# MCU_STM32H723ZGT6.net
KiCad netlist of a schematic drawn in Altium Designer
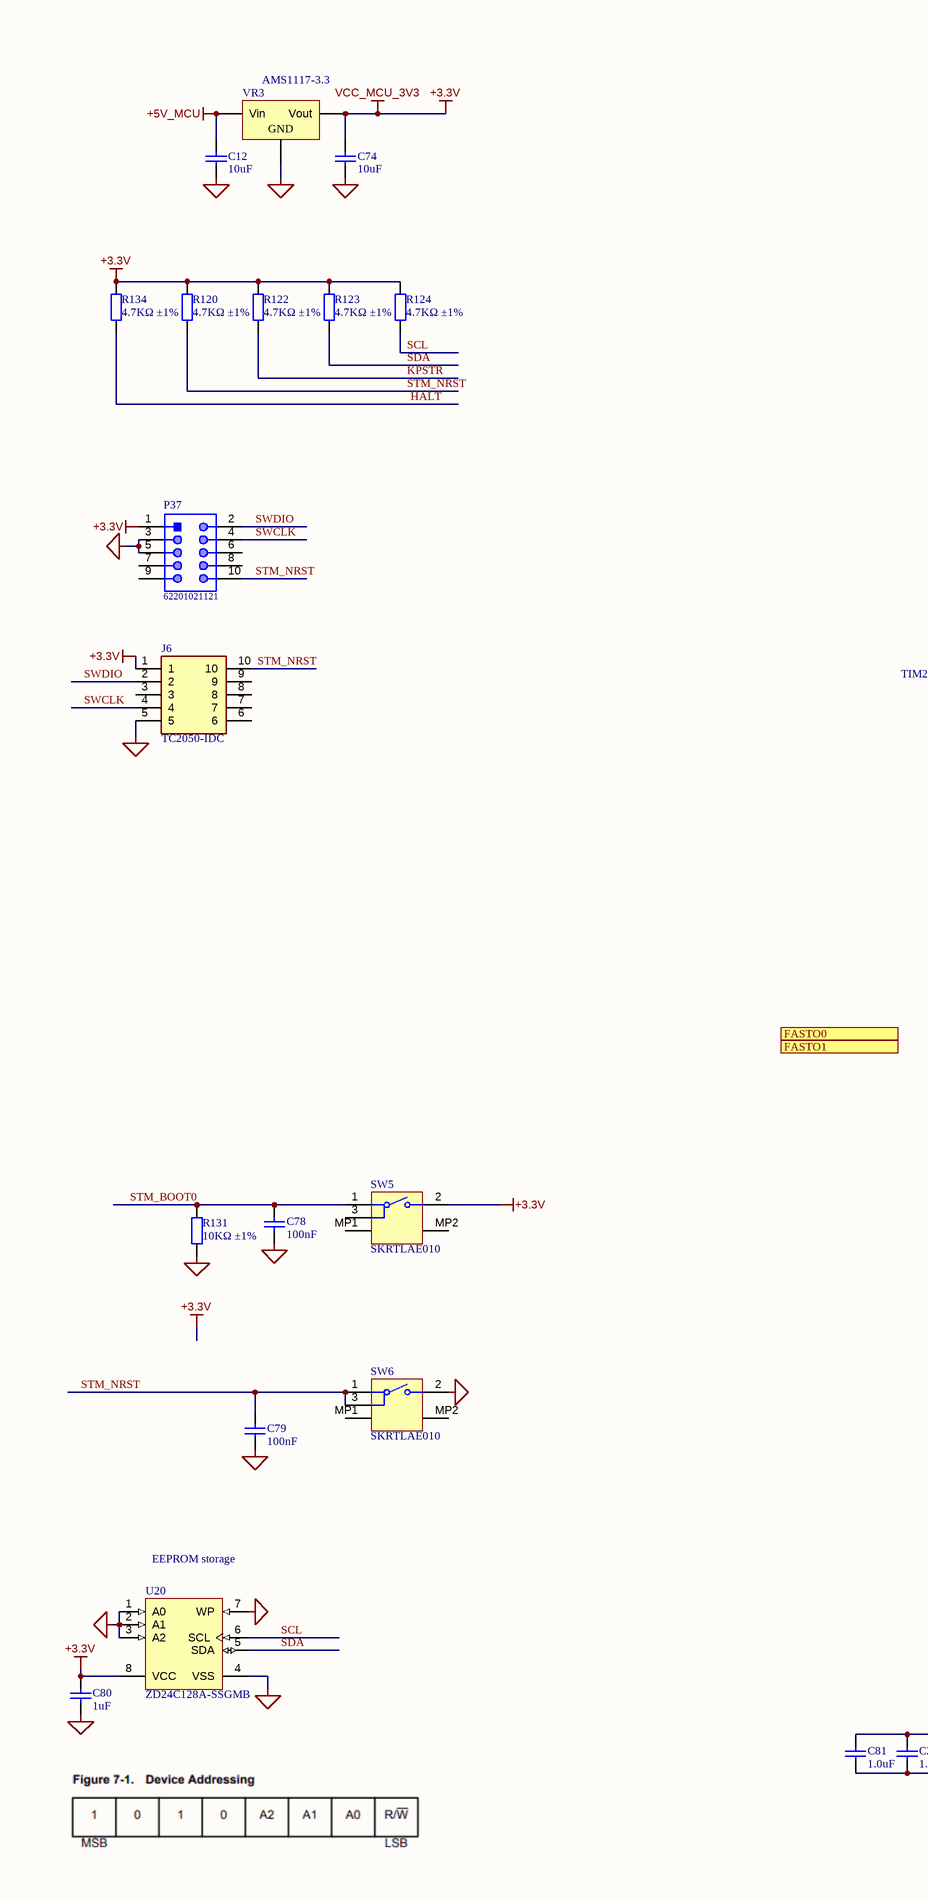
[diagram p0: MCU_STM32H723ZGT6.SchDoc, left]
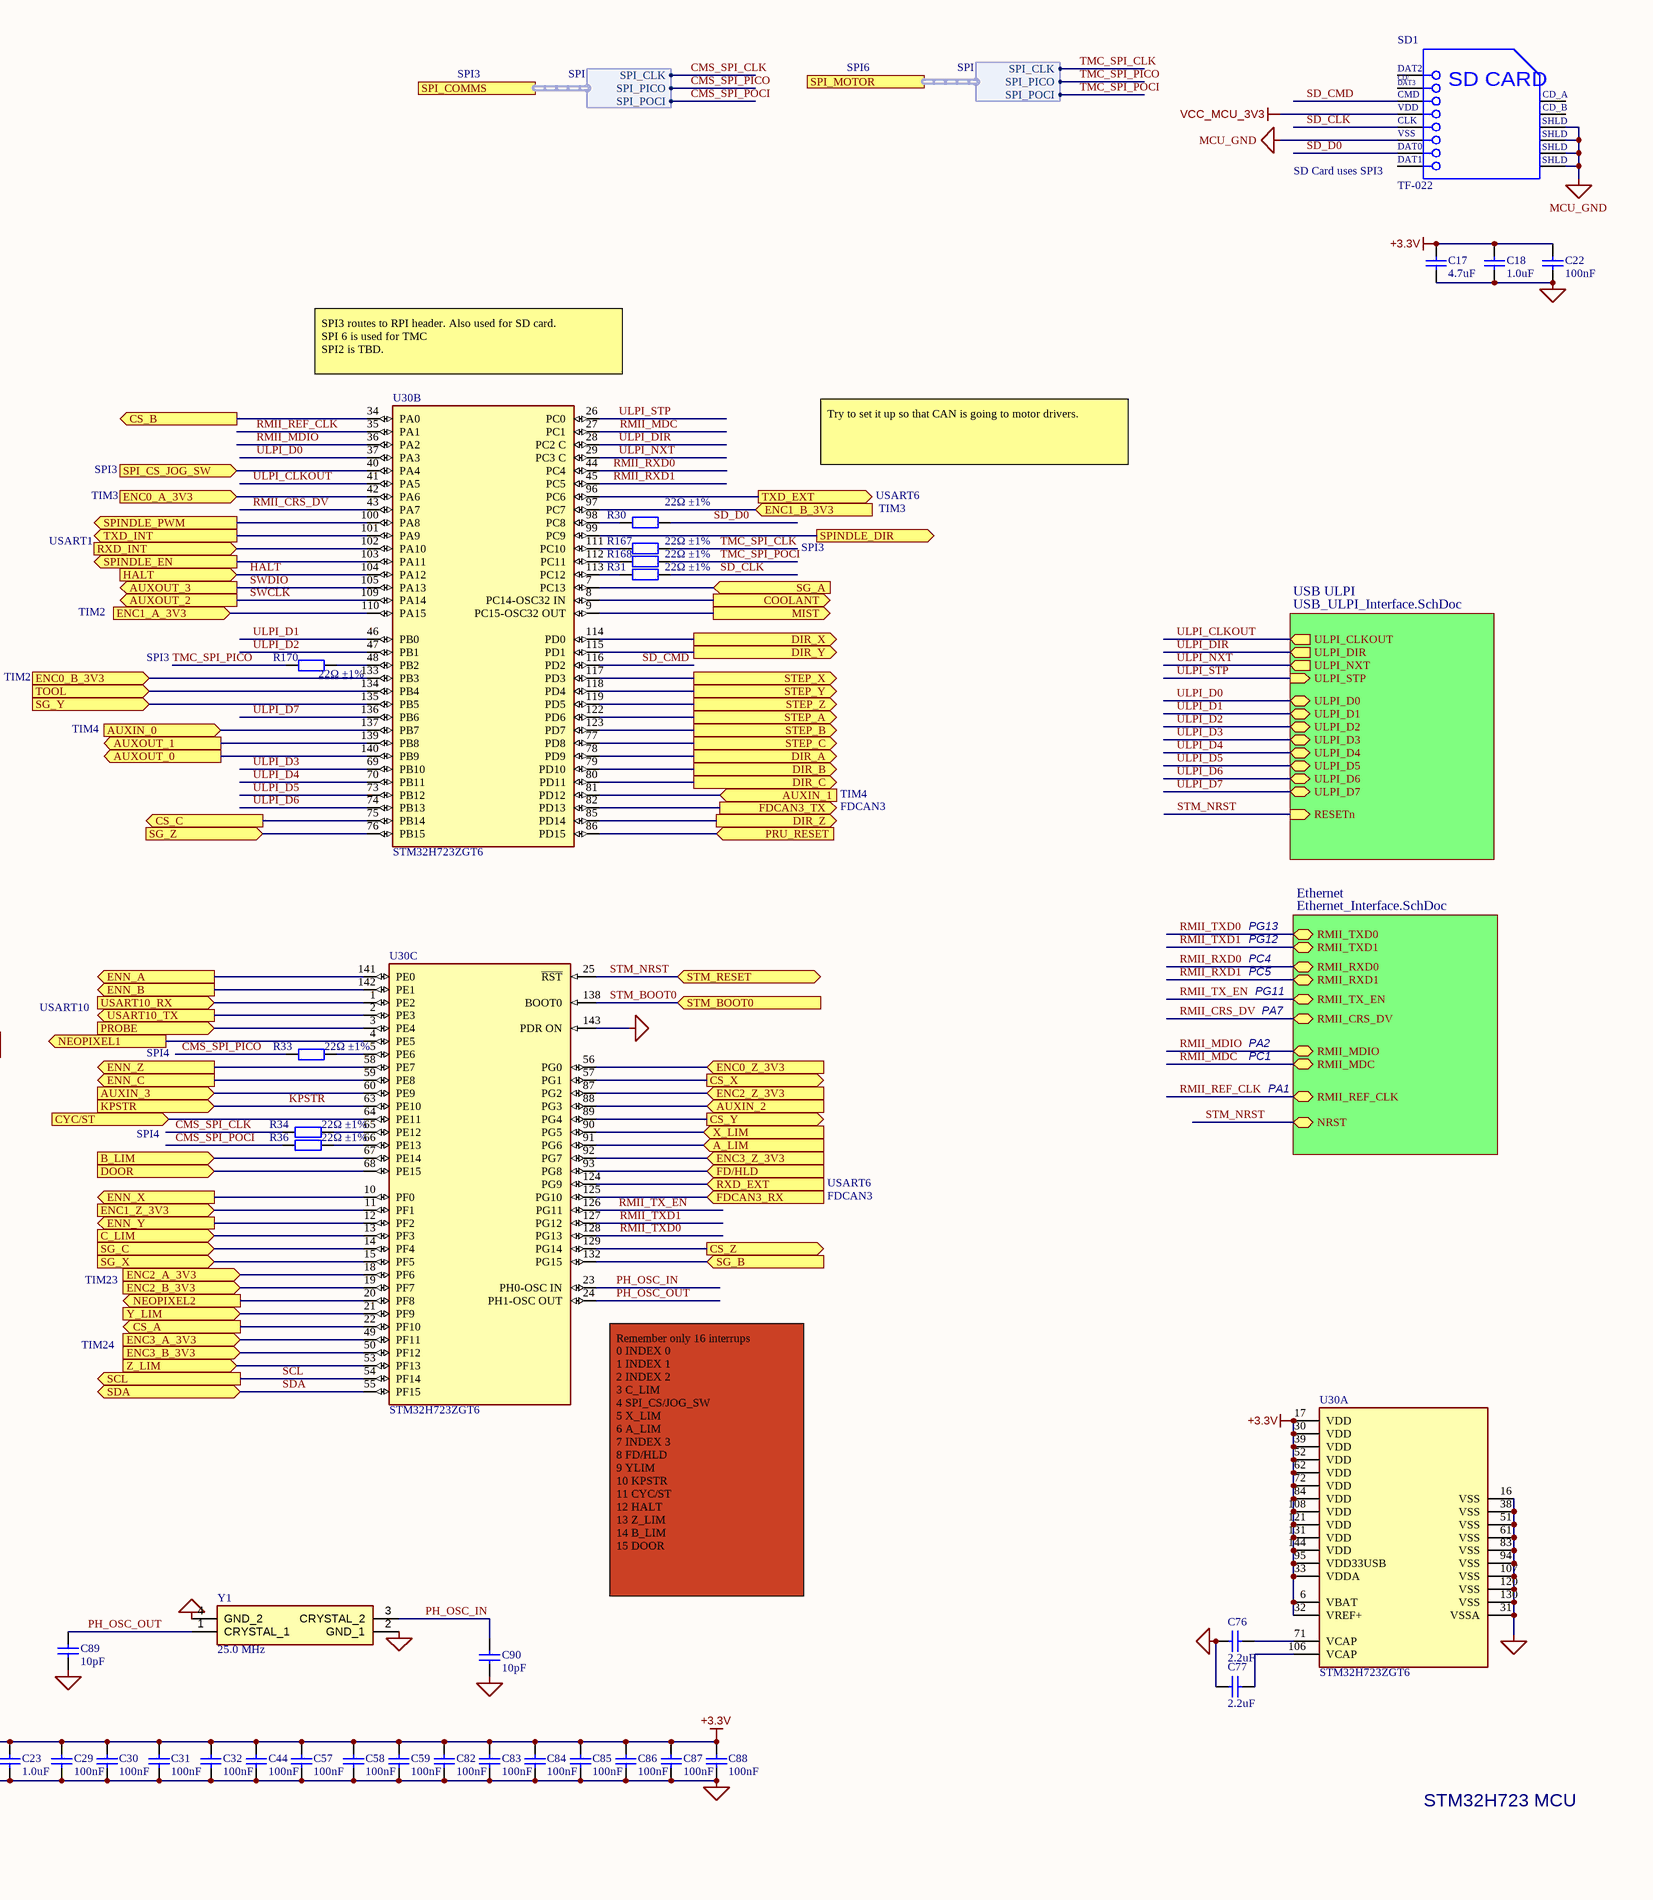
[diagram p1: MCU_STM32H723ZGT6.SchDoc, right]

(export (version "E")
  (design (tool "Eeschema 10.0.6"))
  (components
    (comp (ref "C12")
      (value "10uF")
      (footprint "1206_C")
      (description "Chip capacitors")
      (fields
        (field (name "MANUFACTURER") "Samsung Electro-Mechanics")
        (field (name "PARTNUMBER") "CL31A106KBHNNNE")
      )
      (libsource (lib "Cap") (part "1206 10uF (106) 10% 50V"))
    )
    (comp (ref "C17")
      (value "4.7uF")
      (footprint "0603_C")
      (description "16V 4.7uF X5R ±10% 0603 Multilayer Ceramic Capacitors MLCC - SMD/SMT ROHS")
      (fields (field (name "MANUFACTURER") "Samsung Electro-Mechanics") (field (name "TOLERANCE") "10%"))
      (libsource (lib "Sienci_Labs") (part "0603 4.7uF (475) 10% 16V"))
    )
    (comp (ref "C18")
      (value "1.0uF")
      (footprint "0402_C")
      (description "Chip capacitor")
      (fields (field (name "MANUFACTURER") "Samsung Electro-Mechanics") (field (name "TOLERANCE") "10%"))
      (libsource (lib "Cap") (part "0402 1.0uF (105) 10% 25V"))
    )
    (comp (ref "C22")
      (value "100nF")
      (footprint "0402_C")
      (description "16V 100nF X7R ±10% 0402 Multilayer Ceramic Capacitors MLCC - SMD/SMT ROHS")
      (fields (field (name "MANUFACTURER") "Samsung Electro-Mechanics") (field (name "TOLERANCE") "10%"))
      (libsource (lib "Sienci_Labs") (part "0402 100nF (104) 10% 16V"))
    )
    (comp (ref "C23")
      (value "1.0uF")
      (footprint "0402_C")
      (description "Chip capacitor")
      (fields
        (field (name "MANUFACTURER") "Samsung Electro-Mechanics")
        (field (name "PARTNUMBER") "CL05A105KA5NQNC")
      )
      (libsource (lib "Cap") (part "0402 1.0uF (105) 10% 25V"))
    )
    (comp (ref "C29")
      (value "100nF")
      (footprint "0402_C")
      (description "Chip capacitors")
      (fields
        (field (name "MANUFACTURER") "Samsung Electro-Mechanics")
        (field (name "PARTNUMBER") "CL05B104KO5NNNC")
      )
      (libsource (lib "Cap") (part "0402 100nF (104) 10% 16V"))
    )
    (comp (ref "C30")
      (value "100nF")
      (footprint "0402_C")
      (description "Chip capacitors")
      (fields
        (field (name "MANUFACTURER") "Samsung Electro-Mechanics")
        (field (name "PARTNUMBER") "CL05B104KO5NNNC")
      )
      (libsource (lib "Cap") (part "0402 100nF (104) 10% 16V"))
    )
    (comp (ref "C31")
      (value "100nF")
      (footprint "0402_C")
      (description "Chip capacitors")
      (fields
        (field (name "MANUFACTURER") "Samsung Electro-Mechanics")
        (field (name "PARTNUMBER") "CL05B104KO5NNNC")
      )
      (libsource (lib "Cap") (part "0402 100nF (104) 10% 16V"))
    )
    (comp (ref "C32")
      (value "100nF")
      (footprint "0402_C")
      (description "Chip capacitors")
      (fields
        (field (name "MANUFACTURER") "Samsung Electro-Mechanics")
        (field (name "PARTNUMBER") "CL05B104KO5NNNC")
      )
      (libsource (lib "Cap") (part "0402 100nF (104) 10% 16V"))
    )
    (comp (ref "C44")
      (value "100nF")
      (footprint "0402_C")
      (description "Chip capacitors")
      (fields
        (field (name "MANUFACTURER") "Samsung Electro-Mechanics")
        (field (name "PARTNUMBER") "CL05B104KO5NNNC")
      )
      (libsource (lib "Cap") (part "0402 100nF (104) 10% 16V"))
    )
    (comp (ref "C57")
      (value "100nF")
      (footprint "0402_C")
      (description "Chip capacitors")
      (fields
        (field (name "MANUFACTURER") "Samsung Electro-Mechanics")
        (field (name "PARTNUMBER") "CL05B104KO5NNNC")
      )
      (libsource (lib "Cap") (part "0402 100nF (104) 10% 16V"))
    )
    (comp (ref "C58")
      (value "100nF")
      (footprint "0402_C")
      (description "Chip capacitors")
      (fields
        (field (name "MANUFACTURER") "Samsung Electro-Mechanics")
        (field (name "PARTNUMBER") "CL05B104KO5NNNC")
      )
      (libsource (lib "Cap") (part "0402 100nF (104) 10% 16V"))
    )
    (comp (ref "C59")
      (value "100nF")
      (footprint "0402_C")
      (description "Chip capacitors")
      (fields
        (field (name "MANUFACTURER") "Samsung Electro-Mechanics")
        (field (name "PARTNUMBER") "CL05B104KO5NNNC")
      )
      (libsource (lib "Cap") (part "0402 100nF (104) 10% 16V"))
    )
    (comp (ref "C74")
      (value "10uF")
      (footprint "1206_C")
      (description "Chip capacitors")
      (fields
        (field (name "MANUFACTURER") "Samsung Electro-Mechanics")
        (field (name "PARTNUMBER") "CL31A106KBHNNNE")
      )
      (libsource (lib "Cap") (part "1206 10uF (106) 10% 50V"))
    )
    (comp (ref "C76")
      (value "2.2uF")
      (footprint "0603_C")
      (description "Chip capacitors")
      (fields
        (field (name "MANUFACTURER") "Samsung Electro-Mechanics")
        (field (name "PARTNUMBER") "CL10A225KO8NNNC")
      )
      (libsource (lib "Cap") (part "0603 2.2uF (225) 10% 16V"))
    )
    (comp (ref "C77")
      (value "2.2uF")
      (footprint "0603_C")
      (description "Chip capacitors")
      (fields
        (field (name "MANUFACTURER") "Samsung Electro-Mechanics")
        (field (name "PARTNUMBER") "CL10A225KO8NNNC")
      )
      (libsource (lib "Cap") (part "0603 2.2uF (225) 10% 16V"))
    )
    (comp (ref "C78")
      (value "100nF")
      (footprint "0603_C")
      (description "Chip capacitors")
      (fields (field (name "MANUFACTURER") "YAGEO") (field (name "PARTNUMBER") "CC0603KRX7R9BB104"))
      (libsource (lib "Cap") (part "0603 100nF (104) 10% 50V"))
    )
    (comp (ref "C79")
      (value "100nF")
      (footprint "0603_C")
      (description "Chip capacitors")
      (fields (field (name "MANUFACTURER") "YAGEO") (field (name "PARTNUMBER") "CC0603KRX7R9BB104"))
      (libsource (lib "Cap") (part "0603 100nF (104) 10% 50V"))
    )
    (comp (ref "C80")
      (value "1uF")
      (footprint "0603_C")
      (description "Chip capacitors")
      (fields
        (field (name "MANUFACTURER") "Samsung Electro-Mechanics")
        (field (name "PARTNUMBER") "CL10A105KB8NNNC")
      )
      (libsource (lib "Cap") (part "0603 1uF (105) 10% 50V"))
    )
    (comp (ref "C81")
      (value "1.0uF")
      (footprint "0402_C")
      (description "Chip capacitor")
      (fields
        (field (name "MANUFACTURER") "Samsung Electro-Mechanics")
        (field (name "PARTNUMBER") "CL05A105KA5NQNC")
      )
      (libsource (lib "Cap") (part "0402 1.0uF (105) 10% 25V"))
    )
    (comp (ref "C82")
      (value "100nF")
      (footprint "0402_C")
      (description "Chip capacitors")
      (fields
        (field (name "MANUFACTURER") "Samsung Electro-Mechanics")
        (field (name "PARTNUMBER") "CL05B104KO5NNNC")
      )
      (libsource (lib "Cap") (part "0402 100nF (104) 10% 16V"))
    )
    (comp (ref "C83")
      (value "100nF")
      (footprint "0402_C")
      (description "Chip capacitors")
      (fields
        (field (name "MANUFACTURER") "Samsung Electro-Mechanics")
        (field (name "PARTNUMBER") "CL05B104KO5NNNC")
      )
      (libsource (lib "Cap") (part "0402 100nF (104) 10% 16V"))
    )
    (comp (ref "C84")
      (value "100nF")
      (footprint "0402_C")
      (description "Chip capacitors")
      (fields
        (field (name "MANUFACTURER") "Samsung Electro-Mechanics")
        (field (name "PARTNUMBER") "CL05B104KO5NNNC")
      )
      (libsource (lib "Cap") (part "0402 100nF (104) 10% 16V"))
    )
    (comp (ref "C85")
      (value "100nF")
      (footprint "0402_C")
      (description "Chip capacitors")
      (fields
        (field (name "MANUFACTURER") "Samsung Electro-Mechanics")
        (field (name "PARTNUMBER") "CL05B104KO5NNNC")
      )
      (libsource (lib "Cap") (part "0402 100nF (104) 10% 16V"))
    )
    (comp (ref "C86")
      (value "100nF")
      (footprint "0402_C")
      (description "Chip capacitors")
      (fields
        (field (name "MANUFACTURER") "Samsung Electro-Mechanics")
        (field (name "PARTNUMBER") "CL05B104KO5NNNC")
      )
      (libsource (lib "Cap") (part "0402 100nF (104) 10% 16V"))
    )
    (comp (ref "C87")
      (value "100nF")
      (footprint "0402_C")
      (description "Chip capacitors")
      (fields
        (field (name "MANUFACTURER") "Samsung Electro-Mechanics")
        (field (name "PARTNUMBER") "CL05B104KO5NNNC")
      )
      (libsource (lib "Cap") (part "0402 100nF (104) 10% 16V"))
    )
    (comp (ref "C88")
      (value "100nF")
      (footprint "0402_C")
      (description "Chip capacitors")
      (fields
        (field (name "MANUFACTURER") "Samsung Electro-Mechanics")
        (field (name "PARTNUMBER") "CL05B104KO5NNNC")
      )
      (libsource (lib "Cap") (part "0402 100nF (104) 10% 16V"))
    )
    (comp (ref "C89")
      (value "10pF")
      (footprint "0402_C")
      (description "Chip capacitors")
      (fields
        (field (name "MANUFACTURER") "Samsung Electro-Mechanics")
        (field (name "PARTNUMBER") "CL05C100JB5NNNC")
      )
      (libsource (lib "Cap") (part "0402 10pF (100) 5% 50V"))
    )
    (comp (ref "C90")
      (value "10pF")
      (footprint "0402_C")
      (description "Chip capacitors")
      (fields
        (field (name "MANUFACTURER") "Samsung Electro-Mechanics")
        (field (name "PARTNUMBER") "CL05C100JB5NNNC")
      )
      (libsource (lib "Cap") (part "0402 10pF (100) 5% 50V"))
    )
    (comp (ref "J6")
      (value "TC2050-IDC")
      (footprint "SamacSys:TC2050-IDC")
      (description "Connector")
      (libsource (lib "*") (part "TC2050-IDC"))
    )
    (comp (ref "P37")
      (value "62201021121")
      (footprint "62201021121")
      (description "THT Vertical Pin Header WR-PHD, Pitch 1.27 mm, Dual Row, 10 pins")
      (fields (field (name "MANUFACTURER") "Wurth Elektronik") (field (name "PUBLISHER") "WurthElektronik"))
      (libsource (lib "Altium Content Vault") (part "WE-CN-2P-M-R10"))
    )
    (comp (ref "R30")
      (value "22Ω ±1%")
      (footprint "0402_R")
      (description "Chip resistor")
      (fields (field (name "MANUFACTURER") "Uniroyal Elec") (field (name "PARTNUMBER") "0402WGF220JTCE"))
      (libsource (lib "RES") (part "0402 22R (22R0) 1%"))
    )
    (comp (ref "R31")
      (value "22Ω ±1%")
      (footprint "0402_R")
      (description "Chip resistor")
      (fields (field (name "MANUFACTURER") "Uniroyal Elec") (field (name "PARTNUMBER") "0402WGF220JTCE"))
      (libsource (lib "RES") (part "0402 22R (22R0) 1%"))
    )
    (comp (ref "R33")
      (value "22Ω ±1%")
      (footprint "0402_R")
      (description "Chip resistor")
      (fields (field (name "MANUFACTURER") "Uniroyal Elec") (field (name "PARTNUMBER") "0402WGF220JTCE"))
      (libsource (lib "RES") (part "0402 22R (22R0) 1%"))
    )
    (comp (ref "R34")
      (value "22Ω ±1%")
      (footprint "0402_R")
      (description "Chip resistor")
      (fields (field (name "MANUFACTURER") "Uniroyal Elec") (field (name "PARTNUMBER") "0402WGF220JTCE"))
      (libsource (lib "RES") (part "0402 22R (22R0) 1%"))
    )
    (comp (ref "R36")
      (value "22Ω ±1%")
      (footprint "0402_R")
      (description "Chip resistor")
      (fields (field (name "MANUFACTURER") "Uniroyal Elec") (field (name "PARTNUMBER") "0402WGF220JTCE"))
      (libsource (lib "RES") (part "0402 22R (22R0) 1%"))
    )
    (comp (ref "R120")
      (value "4.7KΩ ±1%")
      (footprint "0603_R")
      (description "Chip resistor")
      (fields (field (name "MANUFACTURER") "Uniroyal Elec") (field (name "PARTNUMBER") "0603WAF4701T5E"))
      (libsource (lib "RES") (part "0603 4.7K (4701) 1%"))
    )
    (comp (ref "R122")
      (value "4.7KΩ ±1%")
      (footprint "0603_R")
      (description "Chip resistor")
      (fields (field (name "MANUFACTURER") "Uniroyal Elec") (field (name "PARTNUMBER") "0603WAF4701T5E"))
      (libsource (lib "RES") (part "0603 4.7K (4701) 1%"))
    )
    (comp (ref "R123")
      (value "4.7KΩ ±1%")
      (footprint "0603_R")
      (description "Chip resistor")
      (fields (field (name "MANUFACTURER") "Uniroyal Elec") (field (name "PARTNUMBER") "0603WAF4701T5E"))
      (libsource (lib "RES") (part "0603 4.7K (4701) 1%"))
    )
    (comp (ref "R124")
      (value "4.7KΩ ±1%")
      (footprint "0603_R")
      (description "Chip resistor")
      (fields (field (name "MANUFACTURER") "Uniroyal Elec") (field (name "PARTNUMBER") "0603WAF4701T5E"))
      (libsource (lib "RES") (part "0603 4.7K (4701) 1%"))
    )
    (comp (ref "R131")
      (value "10KΩ ±1%")
      (footprint "0603_R")
      (description "Chip resistor")
      (fields (field (name "MANUFACTURER") "Uniroyal Elec") (field (name "PARTNUMBER") "0603WAF1002T5E"))
      (libsource (lib "RES") (part "0603 10K (1002) 1%"))
    )
    (comp (ref "R134")
      (value "4.7KΩ ±1%")
      (footprint "0603_R")
      (description "Chip resistor")
      (fields (field (name "MANUFACTURER") "Uniroyal Elec") (field (name "PARTNUMBER") "0603WAF4701T5E"))
      (libsource (lib "RES") (part "0603 4.7K (4701) 1%"))
    )
    (comp (ref "R167")
      (value "22Ω ±1%")
      (footprint "0402_R")
      (description "Chip resistor")
      (fields (field (name "MANUFACTURER") "Uniroyal Elec") (field (name "PARTNUMBER") "0402WGF220JTCE"))
      (libsource (lib "RES") (part "0402 22R (22R0) 1%"))
    )
    (comp (ref "R168")
      (value "22Ω ±1%")
      (footprint "0402_R")
      (description "Chip resistor")
      (fields (field (name "MANUFACTURER") "Uniroyal Elec") (field (name "PARTNUMBER") "0402WGF220JTCE"))
      (libsource (lib "RES") (part "0402 22R (22R0) 1%"))
    )
    (comp (ref "R170")
      (value "22Ω ±1%")
      (footprint "0402_R")
      (description "Chip resistor")
      (fields (field (name "MANUFACTURER") "Uniroyal Elec") (field (name "PARTNUMBER") "0402WGF220JTCE"))
      (libsource (lib "RES") (part "0402 22R (22R0) 1%"))
    )
    (comp (ref "SD1")
      (value "TF-022")
      (footprint "MOLX-503398-1892_V")
      (description "-40℃~+85℃ 1.28mm Gold plating Deck MicroSD card (TF card) Self bomb SMD SD Card Connectors ROHS")
      (fields (field (name "MANUFACTURER") "Hanbo Electronic"))
      (libsource (lib "Sienci_Labs") (part "TF-022"))
    )
    (comp (ref "SW5")
      (value "SKRTLAE010")
      (footprint "ALPS-SKRTLAE010_V")
      (description "Side Push Type, 250 V, -40 to 90 degC, 3-Pin SMD, RoHS, Tape and Reel")
      (fields (field (name "MANUFACTURER") "ALPS"))
      (libsource (lib "Altium Content Vault") (part "SW_SPST-3_A"))
    )
    (comp (ref "SW6")
      (value "SKRTLAE010")
      (footprint "ALPS-SKRTLAE010_V")
      (description "Side Push Type, 250 V, -40 to 90 degC, 3-Pin SMD, RoHS, Tape and Reel")
      (fields (field (name "MANUFACTURER") "ALPS"))
      (libsource (lib "Altium Content Vault") (part "SW_SPST-3_A"))
    )
    (comp (ref "U20")
      (value "ZD24C128A-SSGMB")
      (footprint "SOIC-SN8_L")
      (description "IC EEPROM 128KBIT I2C 8SOIC")
      (libsource (lib "PrintNC_GRBLHAL_Breakout") (part "MEM-SEEPROM-34AA02-IL8"))
    )
    (comp (ref "U30")
      (value "STM32H723ZGT6")
      (footprint "FP-LQFP144-1A-IPC_A")
      (description "IC MCU 32BIT 1MB FLASH 144LQFP")
      (libsource (lib "Universal_CNC_Breakout") (part "STM32H723ZGT6"))
    )
    (comp (ref "VR3")
      (value "AMS1117-3.3")
      (footprint "SOT-223")
      (description "Vout=3.3V 1A 72dB@(120Hz) (LDO)")
      (libsource (lib "LDO") (part "SOT-223 AMS1117-3.3"))
    )
    (comp (ref "Y1")
      (value "25.0 MHz")
      (footprint "SamacSys:YSX321SL")
      (description "Crystal or Oscillator")
      (fields (field (name "MANUFACTURER_PART_NUMBER") "X322525MSB4SI"))
      (libsource (lib "*") (part "YSX321SL"))
    )
  )
  (nets
    (net (code "2") (name "+3.3V") (class "Default")
      (node (ref "C17") (pin "2") (pinfunction "2_2") (pintype "passive"))
      (node (ref "C18") (pin "2") (pinfunction "2_2") (pintype "passive"))
      (node (ref "C22") (pin "2") (pinfunction "2_2") (pintype "passive"))
      (node (ref "C23") (pin "2") (pinfunction "2_2") (pintype "passive"))
      (node (ref "C29") (pin "2") (pinfunction "2_2") (pintype "passive"))
      (node (ref "C30") (pin "2") (pinfunction "2_2") (pintype "passive"))
      (node (ref "C31") (pin "2") (pinfunction "2_2") (pintype "passive"))
      (node (ref "C32") (pin "2") (pinfunction "2_2") (pintype "passive"))
      (node (ref "C44") (pin "2") (pinfunction "2_2") (pintype "passive"))
      (node (ref "C57") (pin "2") (pinfunction "2_2") (pintype "passive"))
      (node (ref "C58") (pin "2") (pinfunction "2_2") (pintype "passive"))
      (node (ref "C59") (pin "2") (pinfunction "2_2") (pintype "passive"))
      (node (ref "C74") (pin "2") (pinfunction "2_2") (pintype "passive"))
      (node (ref "C80") (pin "2") (pinfunction "2_2") (pintype "passive"))
      (node (ref "C81") (pin "2") (pinfunction "2_2") (pintype "passive"))
      (node (ref "C82") (pin "2") (pinfunction "2_2") (pintype "passive"))
      (node (ref "C83") (pin "2") (pinfunction "2_2") (pintype "passive"))
      (node (ref "C84") (pin "2") (pinfunction "2_2") (pintype "passive"))
      (node (ref "C85") (pin "2") (pinfunction "2_2") (pintype "passive"))
      (node (ref "C86") (pin "2") (pinfunction "2_2") (pintype "passive"))
      (node (ref "C87") (pin "2") (pinfunction "2_2") (pintype "passive"))
      (node (ref "C88") (pin "2") (pinfunction "2_2") (pintype "passive"))
      (node (ref "J6") (pin "1") (pinfunction "1_1") (pintype "passive"))
      (node (ref "P37") (pin "1") (pinfunction "1_1") (pintype "passive"))
      (node (ref "R120") (pin "2") (pinfunction "2_2") (pintype "passive"))
      (node (ref "R122") (pin "2") (pinfunction "2_2") (pintype "passive"))
      (node (ref "R123") (pin "2") (pinfunction "2_2") (pintype "passive"))
      (node (ref "R124") (pin "2") (pinfunction "2_2") (pintype "passive"))
      (node (ref "R134") (pin "2") (pinfunction "2_2") (pintype "passive"))
      (node (ref "SD1") (pin "4") (pinfunction "VDD_4") (pintype "passive"))
      (node (ref "SW5") (pin "2") (pinfunction "2_2") (pintype "passive"))
      (node (ref "U20") (pin "8") (pinfunction "VCC_8") (pintype "power_in"))
      (node (ref "U30") (pin "108") (pinfunction "VDD_108") (pintype "power_in"))
      (node (ref "U30") (pin "121") (pinfunction "VDD_121") (pintype "power_in"))
      (node (ref "U30") (pin "131") (pinfunction "VDD_131") (pintype "power_in"))
      (node (ref "U30") (pin "144") (pinfunction "VDD_144") (pintype "power_in"))
      (node (ref "U30") (pin "17") (pinfunction "VDD_17") (pintype "power_in"))
      (node (ref "U30") (pin "30") (pinfunction "VDD_30") (pintype "power_in"))
      (node (ref "U30") (pin "32") (pinfunction "VREF+_32") (pintype "power_in"))
      (node (ref "U30") (pin "33") (pinfunction "VDDA_33") (pintype "power_in"))
      (node (ref "U30") (pin "39") (pinfunction "VDD_39") (pintype "power_in"))
      (node (ref "U30") (pin "52") (pinfunction "VDD_52") (pintype "power_in"))
      (node (ref "U30") (pin "6") (pinfunction "VBAT_6") (pintype "power_in"))
      (node (ref "U30") (pin "62") (pinfunction "VDD_62") (pintype "power_in"))
      (node (ref "U30") (pin "72") (pinfunction "VDD_72") (pintype "power_in"))
      (node (ref "U30") (pin "84") (pinfunction "VDD_84") (pintype "power_in"))
      (node (ref "U30") (pin "95") (pinfunction "VDD33USB_95") (pintype "power_in"))
      (node (ref "VR3") (pin "2") (pinfunction "Vout_2") (pintype "passive"))
    )
    (net (code "3") (name "+5V_MCU") (class "Default")
      (node (ref "C12") (pin "2") (pinfunction "2_2") (pintype "passive"))
      (node (ref "VR3") (pin "3") (pinfunction "Vin_3") (pintype "passive"))
    )
    (net (code "4") (name "/AUXIN_0") (class "Default")
      (node (ref "U30") (pin "137") (pinfunction "PB7_137") (pintype "bidirectional"))
    )
    (net (code "5") (name "/AUXIN_1") (class "Default")
      (node (ref "U30") (pin "81") (pinfunction "PD12_81") (pintype "bidirectional"))
    )
    (net (code "6") (name "/AUXIN_2") (class "Default")
      (node (ref "U30") (pin "88") (pinfunction "PG3_88") (pintype "bidirectional"))
    )
    (net (code "7") (name "/AUXIN_3") (class "Default")
      (node (ref "U30") (pin "60") (pinfunction "PE9_60") (pintype "bidirectional"))
    )
    (net (code "8") (name "/AUXOUT_0") (class "Default")
      (node (ref "U30") (pin "140") (pinfunction "PB9_140") (pintype "bidirectional"))
    )
    (net (code "9") (name "/AUXOUT_1") (class "Default")
      (node (ref "U30") (pin "139") (pinfunction "PB8_139") (pintype "bidirectional"))
    )
    (net (code "10") (name "/A_LIM") (class "Default")
      (node (ref "U30") (pin "91") (pinfunction "PG6_91") (pintype "bidirectional"))
    )
    (net (code "11") (name "/B_LIM") (class "Default")
      (node (ref "U30") (pin "67") (pinfunction "PE14_67") (pintype "bidirectional"))
    )
    (net (code "12") (name "/CMS_SPI_CLK") (class "Default")
      (node (ref "R34") (pin "1") (pinfunction "1_1") (pintype "passive"))
    )
    (net (code "13") (name "/CMS_SPI_PICO") (class "Default")
      (node (ref "R33") (pin "1") (pinfunction "1_1") (pintype "passive"))
    )
    (net (code "14") (name "/CMS_SPI_POCI") (class "Default")
      (node (ref "R36") (pin "1") (pinfunction "1_1") (pintype "passive"))
    )
    (net (code "15") (name "/COOLANT") (class "Default")
      (node (ref "U30") (pin "8") (pinfunction "PC14-OSC32_IN_8") (pintype "bidirectional"))
    )
    (net (code "16") (name "/CS_A") (class "Default")
      (node (ref "U30") (pin "22") (pinfunction "PF10_22") (pintype "bidirectional"))
    )
    (net (code "17") (name "/CS_B") (class "Default")
      (node (ref "U30") (pin "34") (pinfunction "PA0_34") (pintype "bidirectional"))
    )
    (net (code "18") (name "/CS_C") (class "Default")
      (node (ref "U30") (pin "75") (pinfunction "PB14_75") (pintype "bidirectional"))
    )
    (net (code "19") (name "/CS_X") (class "Default")
      (node (ref "U30") (pin "57") (pinfunction "PG1_57") (pintype "bidirectional"))
    )
    (net (code "20") (name "/CS_Y") (class "Default")
      (node (ref "U30") (pin "89") (pinfunction "PG4_89") (pintype "bidirectional"))
    )
    (net (code "21") (name "/CS_Z") (class "Default")
      (node (ref "U30") (pin "129") (pinfunction "PG14_129") (pintype "bidirectional"))
    )
    (net (code "22") (name "/CYC{slash}ST") (class "Default")
      (node (ref "U30") (pin "64") (pinfunction "PE11_64") (pintype "bidirectional"))
    )
    (net (code "23") (name "/C_LIM") (class "Default")
      (node (ref "U30") (pin "13") (pinfunction "PF3_13") (pintype "bidirectional"))
    )
    (net (code "24") (name "/DIR_A") (class "Default")
      (node (ref "U30") (pin "78") (pinfunction "PD9_78") (pintype "bidirectional"))
    )
    (net (code "25") (name "/DIR_B") (class "Default")
      (node (ref "U30") (pin "79") (pinfunction "PD10_79") (pintype "bidirectional"))
    )
    (net (code "26") (name "/DIR_C") (class "Default")
      (node (ref "U30") (pin "80") (pinfunction "PD11_80") (pintype "bidirectional"))
    )
    (net (code "27") (name "/DIR_X") (class "Default")
      (node (ref "U30") (pin "114") (pinfunction "PD0_114") (pintype "bidirectional"))
    )
    (net (code "28") (name "/DIR_Y") (class "Default")
      (node (ref "U30") (pin "115") (pinfunction "PD1_115") (pintype "bidirectional"))
    )
    (net (code "29") (name "/DIR_Z") (class "Default")
      (node (ref "U30") (pin "85") (pinfunction "PD14_85") (pintype "bidirectional"))
    )
    (net (code "30") (name "/DOOR") (class "Default")
      (node (ref "U30") (pin "68") (pinfunction "PE15_68") (pintype "bidirectional"))
    )
    (net (code "31") (name "/ENC0_A_3V3") (class "Default")
      (node (ref "U30") (pin "42") (pinfunction "PA6_42") (pintype "bidirectional"))
    )
    (net (code "32") (name "/ENC0_B_3V3") (class "Default")
      (node (ref "U30") (pin "133") (pinfunction "PB3_133") (pintype "bidirectional"))
    )
    (net (code "33") (name "/ENC0_Z_3V3") (class "Default")
      (node (ref "U30") (pin "56") (pinfunction "PG0_56") (pintype "bidirectional"))
    )
    (net (code "34") (name "/ENC1_A_3V3") (class "Default")
      (node (ref "U30") (pin "110") (pinfunction "PA15_110") (pintype "bidirectional"))
    )
    (net (code "35") (name "/ENC1_B_3V3") (class "Default")
      (node (ref "U30") (pin "97") (pinfunction "PC7_97") (pintype "bidirectional"))
    )
    (net (code "36") (name "/ENC1_Z_3V3") (class "Default")
      (node (ref "U30") (pin "11") (pinfunction "PF1_11") (pintype "bidirectional"))
    )
    (net (code "37") (name "/ENC2_A_3V3") (class "Default")
      (node (ref "U30") (pin "18") (pinfunction "PF6_18") (pintype "bidirectional"))
    )
    (net (code "38") (name "/ENC2_B_3V3") (class "Default")
      (node (ref "U30") (pin "19") (pinfunction "PF7_19") (pintype "bidirectional"))
    )
    (net (code "39") (name "/ENC2_Z_3V3") (class "Default")
      (node (ref "U30") (pin "87") (pinfunction "PG2_87") (pintype "bidirectional"))
    )
    (net (code "40") (name "/ENC3_A_3V3") (class "Default")
      (node (ref "U30") (pin "49") (pinfunction "PF11_49") (pintype "bidirectional"))
    )
    (net (code "41") (name "/ENC3_B_3V3") (class "Default")
      (node (ref "U30") (pin "50") (pinfunction "PF12_50") (pintype "bidirectional"))
    )
    (net (code "42") (name "/ENC3_Z_3V3") (class "Default")
      (node (ref "U30") (pin "92") (pinfunction "PG7_92") (pintype "bidirectional"))
    )
    (net (code "43") (name "/ENN_A") (class "Default")
      (node (ref "U30") (pin "141") (pinfunction "PE0_141") (pintype "bidirectional"))
    )
    (net (code "44") (name "/ENN_B") (class "Default")
      (node (ref "U30") (pin "142") (pinfunction "PE1_142") (pintype "bidirectional"))
    )
    (net (code "45") (name "/ENN_C") (class "Default")
      (node (ref "U30") (pin "59") (pinfunction "PE8_59") (pintype "bidirectional"))
    )
    (net (code "46") (name "/ENN_X") (class "Default")
      (node (ref "U30") (pin "10") (pinfunction "PF0_10") (pintype "bidirectional"))
    )
    (net (code "47") (name "/ENN_Y") (class "Default")
      (node (ref "U30") (pin "12") (pinfunction "PF2_12") (pintype "bidirectional"))
    )
    (net (code "48") (name "/ENN_Z") (class "Default")
      (node (ref "U30") (pin "58") (pinfunction "PE7_58") (pintype "bidirectional"))
    )
    (net (code "51") (name "/FDCAN3_RX") (class "Default")
      (node (ref "U30") (pin "125") (pinfunction "PG10_125") (pintype "bidirectional"))
    )
    (net (code "52") (name "/FDCAN3_TX") (class "Default")
      (node (ref "U30") (pin "82") (pinfunction "PD13_82") (pintype "bidirectional"))
    )
    (net (code "53") (name "/FD{slash}HLD") (class "Default")
      (node (ref "U30") (pin "93") (pinfunction "PG8_93") (pintype "bidirectional"))
    )
    (net (code "54") (name "/HALT") (class "Default")
      (node (ref "R134") (pin "1") (pinfunction "1_1") (pintype "passive"))
      (node (ref "U30") (pin "104") (pinfunction "PA12_104") (pintype "bidirectional"))
    )
    (net (code "55") (name "/KPSTR") (class "Default")
      (node (ref "R122") (pin "1") (pinfunction "1_1") (pintype "passive"))
      (node (ref "U30") (pin "63") (pinfunction "PE10_63") (pintype "bidirectional"))
    )
    (net (code "56") (name "/MIST") (class "Default")
      (node (ref "U30") (pin "9") (pinfunction "PC15-OSC32_OUT_9") (pintype "bidirectional"))
    )
    (net (code "57") (name "/NEOPIXEL1") (class "Default")
      (node (ref "U30") (pin "4") (pinfunction "PE5_4") (pintype "bidirectional"))
    )
    (net (code "58") (name "/NEOPIXEL2") (class "Default")
      (node (ref "U30") (pin "20") (pinfunction "PF8_20") (pintype "bidirectional"))
    )
    (net (code "59") (name "/PH_OSC_IN") (class "Default")
      (node (ref "C90") (pin "2") (pinfunction "2_2") (pintype "passive"))
      (node (ref "U30") (pin "23") (pinfunction "PH0-OSC_IN_23") (pintype "bidirectional"))
      (node (ref "Y1") (pin "3") (pinfunction "CRYSTAL_2_3") (pintype "passive"))
    )
    (net (code "60") (name "/PH_OSC_OUT") (class "Default")
      (node (ref "C89") (pin "2") (pinfunction "2_2") (pintype "passive"))
      (node (ref "U30") (pin "24") (pinfunction "PH1-OSC_OUT_24") (pintype "bidirectional"))
      (node (ref "Y1") (pin "1") (pinfunction "CRYSTAL_1_1") (pintype "passive"))
    )
    (net (code "61") (name "/PROBE") (class "Default")
      (node (ref "U30") (pin "3") (pinfunction "PE4_3") (pintype "bidirectional"))
    )
    (net (code "62") (name "/PRU_RESET") (class "Default")
      (node (ref "U30") (pin "86") (pinfunction "PD15_86") (pintype "bidirectional"))
    )
    (net (code "63") (name "/RMII_CRS_DV") (class "Default")
      (node (ref "U30") (pin "43") (pinfunction "PA7_43") (pintype "bidirectional"))
    )
    (net (code "64") (name "/RMII_MDC") (class "Default")
      (node (ref "U30") (pin "27") (pinfunction "PC1_27") (pintype "bidirectional"))
    )
    (net (code "65") (name "/RMII_MDIO") (class "Default")
      (node (ref "U30") (pin "36") (pinfunction "PA2_36") (pintype "bidirectional"))
    )
    (net (code "66") (name "/RMII_REF_CLK") (class "Default")
      (node (ref "U30") (pin "35") (pinfunction "PA1_35") (pintype "bidirectional"))
    )
    (net (code "67") (name "/RMII_RXD0") (class "Default")
      (node (ref "U30") (pin "44") (pinfunction "PC4_44") (pintype "bidirectional"))
    )
    (net (code "68") (name "/RMII_RXD1") (class "Default")
      (node (ref "U30") (pin "45") (pinfunction "PC5_45") (pintype "bidirectional"))
    )
    (net (code "69") (name "/RMII_TXD0") (class "Default")
      (node (ref "U30") (pin "128") (pinfunction "PG13_128") (pintype "bidirectional"))
    )
    (net (code "70") (name "/RMII_TXD1") (class "Default")
      (node (ref "U30") (pin "127") (pinfunction "PG12_127") (pintype "bidirectional"))
    )
    (net (code "71") (name "/RMII_TX_EN") (class "Default")
      (node (ref "U30") (pin "126") (pinfunction "PG11_126") (pintype "bidirectional"))
    )
    (net (code "72") (name "/RXD_EXT") (class "Default")
      (node (ref "U30") (pin "124") (pinfunction "PG9_124") (pintype "bidirectional"))
    )
    (net (code "73") (name "/RXD_INT") (class "Default")
      (node (ref "U30") (pin "102") (pinfunction "PA10_102") (pintype "bidirectional"))
    )
    (net (code "74") (name "/SCL") (class "Default")
      (node (ref "R124") (pin "1") (pinfunction "1_1") (pintype "passive"))
      (node (ref "U20") (pin "6") (pinfunction "SCL_6") (pintype "input"))
      (node (ref "U30") (pin "54") (pinfunction "PF14_54") (pintype "bidirectional"))
    )
    (net (code "75") (name "/SDA") (class "Default")
      (node (ref "R123") (pin "1") (pinfunction "1_1") (pintype "passive"))
      (node (ref "U20") (pin "5") (pinfunction "SDA_5") (pintype "bidirectional"))
      (node (ref "U30") (pin "55") (pinfunction "PF15_55") (pintype "bidirectional"))
    )
    (net (code "76") (name "/SD_CLK") (class "Default")
      (node (ref "R31") (pin "2") (pinfunction "2_2") (pintype "passive"))
      (node (ref "SD1") (pin "5") (pinfunction "CLK_5") (pintype "passive"))
    )
    (net (code "77") (name "/SD_CMD") (class "Default")
      (node (ref "SD1") (pin "3") (pinfunction "CMD_3") (pintype "passive"))
      (node (ref "U30") (pin "116") (pinfunction "PD2_116") (pintype "bidirectional"))
    )
    (net (code "78") (name "/SD_D0") (class "Default")
      (node (ref "R30") (pin "2") (pinfunction "2_2") (pintype "passive"))
      (node (ref "SD1") (pin "7") (pinfunction "DAT0_7") (pintype "passive"))
    )
    (net (code "79") (name "/SG_A") (class "Default")
      (node (ref "U30") (pin "7") (pinfunction "PC13_7") (pintype "bidirectional"))
    )
    (net (code "80") (name "/SG_B") (class "Default")
      (node (ref "U30") (pin "132") (pinfunction "PG15_132") (pintype "bidirectional"))
    )
    (net (code "81") (name "/SG_C") (class "Default")
      (node (ref "U30") (pin "14") (pinfunction "PF4_14") (pintype "bidirectional"))
    )
    (net (code "82") (name "/SG_X") (class "Default")
      (node (ref "U30") (pin "15") (pinfunction "PF5_15") (pintype "bidirectional"))
    )
    (net (code "83") (name "/SG_Y") (class "Default")
      (node (ref "U30") (pin "135") (pinfunction "PB5_135") (pintype "bidirectional"))
    )
    (net (code "84") (name "/SG_Z") (class "Default")
      (node (ref "U30") (pin "76") (pinfunction "PB15_76") (pintype "bidirectional"))
    )
    (net (code "85") (name "/SPINDLE_DIR") (class "Default")
      (node (ref "U30") (pin "99") (pinfunction "PC9_99") (pintype "bidirectional"))
    )
    (net (code "86") (name "/SPINDLE_EN") (class "Default")
      (node (ref "U30") (pin "103") (pinfunction "PA11_103") (pintype "bidirectional"))
    )
    (net (code "87") (name "/SPINDLE_PWM") (class "Default")
      (node (ref "U30") (pin "100") (pinfunction "PA8_100") (pintype "bidirectional"))
    )
    (net (code "88") (name "/SPI_CS_JOG_SW") (class "Default")
      (node (ref "U30") (pin "40") (pinfunction "PA4_40") (pintype "bidirectional"))
    )
    (net (code "89") (name "/STEP_A") (class "Default")
      (node (ref "U30") (pin "122") (pinfunction "PD6_122") (pintype "bidirectional"))
    )
    (net (code "90") (name "/STEP_B") (class "Default")
      (node (ref "U30") (pin "123") (pinfunction "PD7_123") (pintype "bidirectional"))
    )
    (net (code "91") (name "/STEP_C") (class "Default")
      (node (ref "U30") (pin "77") (pinfunction "PD8_77") (pintype "bidirectional"))
    )
    (net (code "92") (name "/STEP_X") (class "Default")
      (node (ref "U30") (pin "117") (pinfunction "PD3_117") (pintype "bidirectional"))
    )
    (net (code "93") (name "/STEP_Y") (class "Default")
      (node (ref "U30") (pin "118") (pinfunction "PD4_118") (pintype "bidirectional"))
    )
    (net (code "94") (name "/STEP_Z") (class "Default")
      (node (ref "U30") (pin "119") (pinfunction "PD5_119") (pintype "bidirectional"))
    )
    (net (code "95") (name "/STM_BOOT0") (class "Default")
      (node (ref "C78") (pin "2") (pinfunction "2_2") (pintype "passive"))
      (node (ref "R131") (pin "1") (pinfunction "1_1") (pintype "passive"))
      (node (ref "SW5") (pin "1") (pinfunction "1_1") (pintype "passive"))
      (node (ref "U30") (pin "138") (pinfunction "BOOT0_138") (pintype "input"))
    )
    (net (code "96") (name "/STM_NRST") (class "Default")
      (node (ref "C79") (pin "2") (pinfunction "2_2") (pintype "passive"))
      (node (ref "J6") (pin "10") (pinfunction "10_10") (pintype "passive"))
      (node (ref "P37") (pin "10") (pinfunction "10_10") (pintype "passive"))
      (node (ref "R120") (pin "1") (pinfunction "1_1") (pintype "passive"))
      (node (ref "SW6") (pin "1") (pinfunction "1_1") (pintype "passive"))
      (node (ref "SW6") (pin "3") (pinfunction "3_3") (pintype "passive"))
      (node (ref "U30") (pin "25") (pinfunction "~{RST}_25") (pintype "input"))
    )
    (net (code "97") (name "/SWCLK") (class "Default")
      (node (ref "J6") (pin "4") (pinfunction "4_4") (pintype "passive"))
      (node (ref "P37") (pin "4") (pinfunction "4_4") (pintype "passive"))
      (node (ref "U30") (pin "109") (pinfunction "PA14_109") (pintype "bidirectional"))
    )
    (net (code "98") (name "/SWDIO") (class "Default")
      (node (ref "J6") (pin "2") (pinfunction "2_2") (pintype "passive"))
      (node (ref "P37") (pin "2") (pinfunction "2_2") (pintype "passive"))
      (node (ref "U30") (pin "105") (pinfunction "PA13_105") (pintype "bidirectional"))
    )
    (net (code "99") (name "/TMC_SPI_CLK") (class "Default")
      (node (ref "R167") (pin "2") (pinfunction "2_2") (pintype "passive"))
    )
    (net (code "100") (name "/TMC_SPI_PICO") (class "Default")
      (node (ref "R170") (pin "1") (pinfunction "1_1") (pintype "passive"))
    )
    (net (code "101") (name "/TMC_SPI_POCI") (class "Default")
      (node (ref "R168") (pin "2") (pinfunction "2_2") (pintype "passive"))
    )
    (net (code "102") (name "/TOOL") (class "Default")
      (node (ref "U30") (pin "134") (pinfunction "PB4_134") (pintype "bidirectional"))
    )
    (net (code "103") (name "/TXD_EXT") (class "Default")
      (node (ref "U30") (pin "96") (pinfunction "PC6_96") (pintype "bidirectional"))
    )
    (net (code "104") (name "/TXD_INT") (class "Default")
      (node (ref "U30") (pin "101") (pinfunction "PA9_101") (pintype "bidirectional"))
    )
    (net (code "105") (name "/ULPI_CLKOUT") (class "Default")
      (node (ref "U30") (pin "41") (pinfunction "PA5_41") (pintype "bidirectional"))
    )
    (net (code "106") (name "/ULPI_D0") (class "Default")
      (node (ref "U30") (pin "37") (pinfunction "PA3_37") (pintype "bidirectional"))
    )
    (net (code "107") (name "/ULPI_D1") (class "Default")
      (node (ref "U30") (pin "46") (pinfunction "PB0_46") (pintype "bidirectional"))
    )
    (net (code "108") (name "/ULPI_D2") (class "Default")
      (node (ref "U30") (pin "47") (pinfunction "PB1_47") (pintype "bidirectional"))
    )
    (net (code "109") (name "/ULPI_D3") (class "Default")
      (node (ref "U30") (pin "69") (pinfunction "PB10_69") (pintype "bidirectional"))
    )
    (net (code "110") (name "/ULPI_D4") (class "Default")
      (node (ref "U30") (pin "70") (pinfunction "PB11_70") (pintype "bidirectional"))
    )
    (net (code "111") (name "/ULPI_D5") (class "Default")
      (node (ref "U30") (pin "73") (pinfunction "PB12_73") (pintype "bidirectional"))
    )
    (net (code "112") (name "/ULPI_D6") (class "Default")
      (node (ref "U30") (pin "74") (pinfunction "PB13_74") (pintype "bidirectional"))
    )
    (net (code "113") (name "/ULPI_D7") (class "Default")
      (node (ref "U30") (pin "136") (pinfunction "PB6_136") (pintype "bidirectional"))
    )
    (net (code "114") (name "/ULPI_DIR") (class "Default")
      (node (ref "U30") (pin "28") (pinfunction "PC2_C_28") (pintype "bidirectional"))
    )
    (net (code "115") (name "/ULPI_NXT") (class "Default")
      (node (ref "U30") (pin "29") (pinfunction "PC3_C_29") (pintype "bidirectional"))
    )
    (net (code "116") (name "/ULPI_STP") (class "Default")
      (node (ref "U30") (pin "26") (pinfunction "PC0_26") (pintype "bidirectional"))
    )
    (net (code "117") (name "/USART10_RX") (class "Default")
      (node (ref "U30") (pin "1") (pinfunction "PE2_1") (pintype "bidirectional"))
    )
    (net (code "118") (name "/USART10_TX") (class "Default")
      (node (ref "U30") (pin "2") (pinfunction "PE3_2") (pintype "bidirectional"))
    )
    (net (code "119") (name "/X_LIM") (class "Default")
      (node (ref "U30") (pin "90") (pinfunction "PG5_90") (pintype "bidirectional"))
    )
    (net (code "120") (name "/Y_LIM") (class "Default")
      (node (ref "U30") (pin "21") (pinfunction "PF9_21") (pintype "bidirectional"))
    )
    (net (code "121") (name "/Z_LIM") (class "Default")
      (node (ref "U30") (pin "53") (pinfunction "PF13_53") (pintype "bidirectional"))
    )
    (net (code "123") (name "MCU_GND") (class "Default")
      (node (ref "C12") (pin "1") (pinfunction "1_1") (pintype "passive"))
      (node (ref "C17") (pin "1") (pinfunction "1_1") (pintype "passive"))
      (node (ref "C18") (pin "1") (pinfunction "1_1") (pintype "passive"))
      (node (ref "C22") (pin "1") (pinfunction "1_1") (pintype "passive"))
      (node (ref "C23") (pin "1") (pinfunction "1_1") (pintype "passive"))
      (node (ref "C29") (pin "1") (pinfunction "1_1") (pintype "passive"))
      (node (ref "C30") (pin "1") (pinfunction "1_1") (pintype "passive"))
      (node (ref "C31") (pin "1") (pinfunction "1_1") (pintype "passive"))
      (node (ref "C32") (pin "1") (pinfunction "1_1") (pintype "passive"))
      (node (ref "C44") (pin "1") (pinfunction "1_1") (pintype "passive"))
      (node (ref "C57") (pin "1") (pinfunction "1_1") (pintype "passive"))
      (node (ref "C58") (pin "1") (pinfunction "1_1") (pintype "passive"))
      (node (ref "C59") (pin "1") (pinfunction "1_1") (pintype "passive"))
      (node (ref "C74") (pin "1") (pinfunction "1_1") (pintype "passive"))
      (node (ref "C76") (pin "1") (pinfunction "1_1") (pintype "passive"))
      (node (ref "C77") (pin "1") (pinfunction "1_1") (pintype "passive"))
      (node (ref "C78") (pin "1") (pinfunction "1_1") (pintype "passive"))
      (node (ref "C79") (pin "1") (pinfunction "1_1") (pintype "passive"))
      (node (ref "C80") (pin "1") (pinfunction "1_1") (pintype "passive"))
      (node (ref "C81") (pin "1") (pinfunction "1_1") (pintype "passive"))
      (node (ref "C82") (pin "1") (pinfunction "1_1") (pintype "passive"))
      (node (ref "C83") (pin "1") (pinfunction "1_1") (pintype "passive"))
      (node (ref "C84") (pin "1") (pinfunction "1_1") (pintype "passive"))
      (node (ref "C85") (pin "1") (pinfunction "1_1") (pintype "passive"))
      (node (ref "C86") (pin "1") (pinfunction "1_1") (pintype "passive"))
      (node (ref "C87") (pin "1") (pinfunction "1_1") (pintype "passive"))
      (node (ref "C88") (pin "1") (pinfunction "1_1") (pintype "passive"))
      (node (ref "C89") (pin "1") (pinfunction "1_1") (pintype "passive"))
      (node (ref "C90") (pin "1") (pinfunction "1_1") (pintype "passive"))
      (node (ref "J6") (pin "5") (pinfunction "5_5") (pintype "passive"))
      (node (ref "P37") (pin "3") (pinfunction "3_3") (pintype "passive"))
      (node (ref "P37") (pin "5") (pinfunction "5_5") (pintype "passive"))
      (node (ref "R131") (pin "2") (pinfunction "2_2") (pintype "passive"))
      (node (ref "SD1") (pin "11") (pinfunction "SHLD_11") (pintype "passive"))
      (node (ref "SD1") (pin "12") (pinfunction "SHLD_12") (pintype "passive"))
      (node (ref "SD1") (pin "13") (pinfunction "SHLD_13") (pintype "passive"))
      (node (ref "SD1") (pin "14") (pinfunction "SHLD_14") (pintype "passive"))
      (node (ref "SD1") (pin "6") (pinfunction "VSS_6") (pintype "passive"))
      (node (ref "SW6") (pin "2") (pinfunction "2_2") (pintype "passive"))
      (node (ref "U20") (pin "1") (pinfunction "A0_1") (pintype "input"))
      (node (ref "U20") (pin "2") (pinfunction "A1_2") (pintype "input"))
      (node (ref "U20") (pin "3") (pinfunction "A2_3") (pintype "input"))
      (node (ref "U20") (pin "4") (pinfunction "VSS_4") (pintype "power_in"))
      (node (ref "U20") (pin "7") (pinfunction "WP_7") (pintype "input"))
      (node (ref "U30") (pin "107") (pinfunction "VSS_107") (pintype "power_in"))
      (node (ref "U30") (pin "120") (pinfunction "VSS_120") (pintype "power_in"))
      (node (ref "U30") (pin "130") (pinfunction "VSS_130") (pintype "power_in"))
      (node (ref "U30") (pin "143") (pinfunction "PDR_ON_143") (pintype "input"))
      (node (ref "U30") (pin "16") (pinfunction "VSS_16") (pintype "power_in"))
      (node (ref "U30") (pin "31") (pinfunction "VSSA_31") (pintype "power_in"))
      (node (ref "U30") (pin "38") (pinfunction "VSS_38") (pintype "power_in"))
      (node (ref "U30") (pin "51") (pinfunction "VSS_51") (pintype "power_in"))
      (node (ref "U30") (pin "61") (pinfunction "VSS_61") (pintype "power_in"))
      (node (ref "U30") (pin "83") (pinfunction "VSS_83") (pintype "power_in"))
      (node (ref "U30") (pin "94") (pinfunction "VSS_94") (pintype "power_in"))
      (node (ref "VR3") (pin "1") (pinfunction "GND_1") (pintype "passive"))
      (node (ref "Y1") (pin "2") (pinfunction "GND_1_2") (pintype "passive"))
      (node (ref "Y1") (pin "4") (pinfunction "GND_2_4") (pintype "passive"))
    )
    (net (code "124") (name "Net-(C76-Pad2)") (class "Default")
      (node (ref "C76") (pin "2") (pinfunction "2_2") (pintype "passive"))
      (node (ref "U30") (pin "71") (pinfunction "VCAP_71") (pintype "power_in"))
    )
    (net (code "125") (name "Net-(C77-Pad2)") (class "Default")
      (node (ref "C77") (pin "2") (pinfunction "2_2") (pintype "passive"))
      (node (ref "U30") (pin "106") (pinfunction "VCAP_106") (pintype "power_in"))
    )
    (net (code "126") (name "Net-(U30B-PB2)") (class "Default")
      (node (ref "R170") (pin "2") (pinfunction "2_2") (pintype "passive"))
      (node (ref "U30") (pin "48") (pinfunction "PB2_48") (pintype "bidirectional"))
    )
    (net (code "127") (name "Net-(U30B-PC8)") (class "Default")
      (node (ref "R30") (pin "1") (pinfunction "1_1") (pintype "passive"))
      (node (ref "U30") (pin "98") (pinfunction "PC8_98") (pintype "bidirectional"))
    )
    (net (code "128") (name "Net-(U30B-PC10)") (class "Default")
      (node (ref "R167") (pin "1") (pinfunction "1_1") (pintype "passive"))
      (node (ref "U30") (pin "111") (pinfunction "PC10_111") (pintype "bidirectional"))
    )
    (net (code "129") (name "Net-(U30B-PC11)") (class "Default")
      (node (ref "R168") (pin "1") (pinfunction "1_1") (pintype "passive"))
      (node (ref "U30") (pin "112") (pinfunction "PC11_112") (pintype "bidirectional"))
    )
    (net (code "130") (name "Net-(U30B-PC12)") (class "Default")
      (node (ref "R31") (pin "1") (pinfunction "1_1") (pintype "passive"))
      (node (ref "U30") (pin "113") (pinfunction "PC12_113") (pintype "bidirectional"))
    )
    (net (code "131") (name "Net-(U30C-PE6)") (class "Default")
      (node (ref "R33") (pin "2") (pinfunction "2_2") (pintype "passive"))
      (node (ref "U30") (pin "5") (pinfunction "PE6_5") (pintype "bidirectional"))
    )
    (net (code "132") (name "Net-(U30C-PE12)") (class "Default")
      (node (ref "R34") (pin "2") (pinfunction "2_2") (pintype "passive"))
      (node (ref "U30") (pin "65") (pinfunction "PE12_65") (pintype "bidirectional"))
    )
    (net (code "133") (name "Net-(U30C-PE13)") (class "Default")
      (node (ref "R36") (pin "2") (pinfunction "2_2") (pintype "passive"))
      (node (ref "U30") (pin "66") (pinfunction "PE13_66") (pintype "bidirectional"))
    )
    (net (code "134") (name "unconnected-(J6-Pad3)") (class "Default")
      (node (ref "J6") (pin "3") (pinfunction "3_3") (pintype "passive"))
    )
    (net (code "135") (name "unconnected-(J6-Pad6)") (class "Default")
      (node (ref "J6") (pin "6") (pinfunction "6_6") (pintype "passive"))
    )
    (net (code "136") (name "unconnected-(J6-Pad7)") (class "Default")
      (node (ref "J6") (pin "7") (pinfunction "7_7") (pintype "passive"))
    )
    (net (code "137") (name "unconnected-(J6-Pad8)") (class "Default")
      (node (ref "J6") (pin "8") (pinfunction "8_8") (pintype "passive"))
    )
    (net (code "138") (name "unconnected-(J6-Pad9)") (class "Default")
      (node (ref "J6") (pin "9") (pinfunction "9_9") (pintype "passive"))
    )
    (net (code "139") (name "unconnected-(P37-Pad6)") (class "Default")
      (node (ref "P37") (pin "6") (pinfunction "6_6") (pintype "passive"))
    )
    (net (code "140") (name "unconnected-(P37-Pad7)") (class "Default")
      (node (ref "P37") (pin "7") (pinfunction "7_7") (pintype "passive"))
    )
    (net (code "141") (name "unconnected-(P37-Pad8)") (class "Default")
      (node (ref "P37") (pin "8") (pinfunction "8_8") (pintype "passive"))
    )
    (net (code "142") (name "unconnected-(P37-Pad9)") (class "Default")
      (node (ref "P37") (pin "9") (pinfunction "9_9") (pintype "passive"))
    )
    (net (code "143") (name "unconnected-(SD1-CD_A-Pad9)") (class "Default")
      (node (ref "SD1") (pin "9") (pinfunction "CD_A_9") (pintype "passive"))
    )
    (net (code "144") (name "unconnected-(SD1-CD_B-Pad10)") (class "Default")
      (node (ref "SD1") (pin "10") (pinfunction "CD_B_10") (pintype "passive"))
    )
    (net (code "145") (name "unconnected-(SD1-CD{slash}DAT3-Pad2)") (class "Default")
      (node (ref "SD1") (pin "2") (pinfunction "CD/DAT3_2") (pintype "passive"))
    )
    (net (code "146") (name "unconnected-(SD1-DAT1-Pad8)") (class "Default")
      (node (ref "SD1") (pin "8") (pinfunction "DAT1_8") (pintype "passive"))
    )
    (net (code "147") (name "unconnected-(SD1-DAT2-Pad1)") (class "Default")
      (node (ref "SD1") (pin "1") (pinfunction "DAT2_1") (pintype "passive"))
    )
    (net (code "148") (name "unconnected-(SW5-Pad3)") (class "Default")
      (node (ref "SW5") (pin "3") (pinfunction "3_3") (pintype "passive"))
    )
    (net (code "149") (name "unconnected-(SW5-PadMP1)") (class "Default")
      (node (ref "SW5") (pin "MP1") (pinfunction "MP1_MP1") (pintype "passive"))
    )
    (net (code "150") (name "unconnected-(SW5-PadMP2)") (class "Default")
      (node (ref "SW5") (pin "MP2") (pinfunction "MP2_MP2") (pintype "passive"))
    )
    (net (code "151") (name "unconnected-(SW6-PadMP1)") (class "Default")
      (node (ref "SW6") (pin "MP1") (pinfunction "MP1_MP1") (pintype "passive"))
    )
    (net (code "152") (name "unconnected-(SW6-PadMP2)") (class "Default")
      (node (ref "SW6") (pin "MP2") (pinfunction "MP2_MP2") (pintype "passive"))
    )
  )
)
